# Qwiic_Shield_for_Teensy_Extended.net
KiCad netlist of a schematic drawn in EAGLE
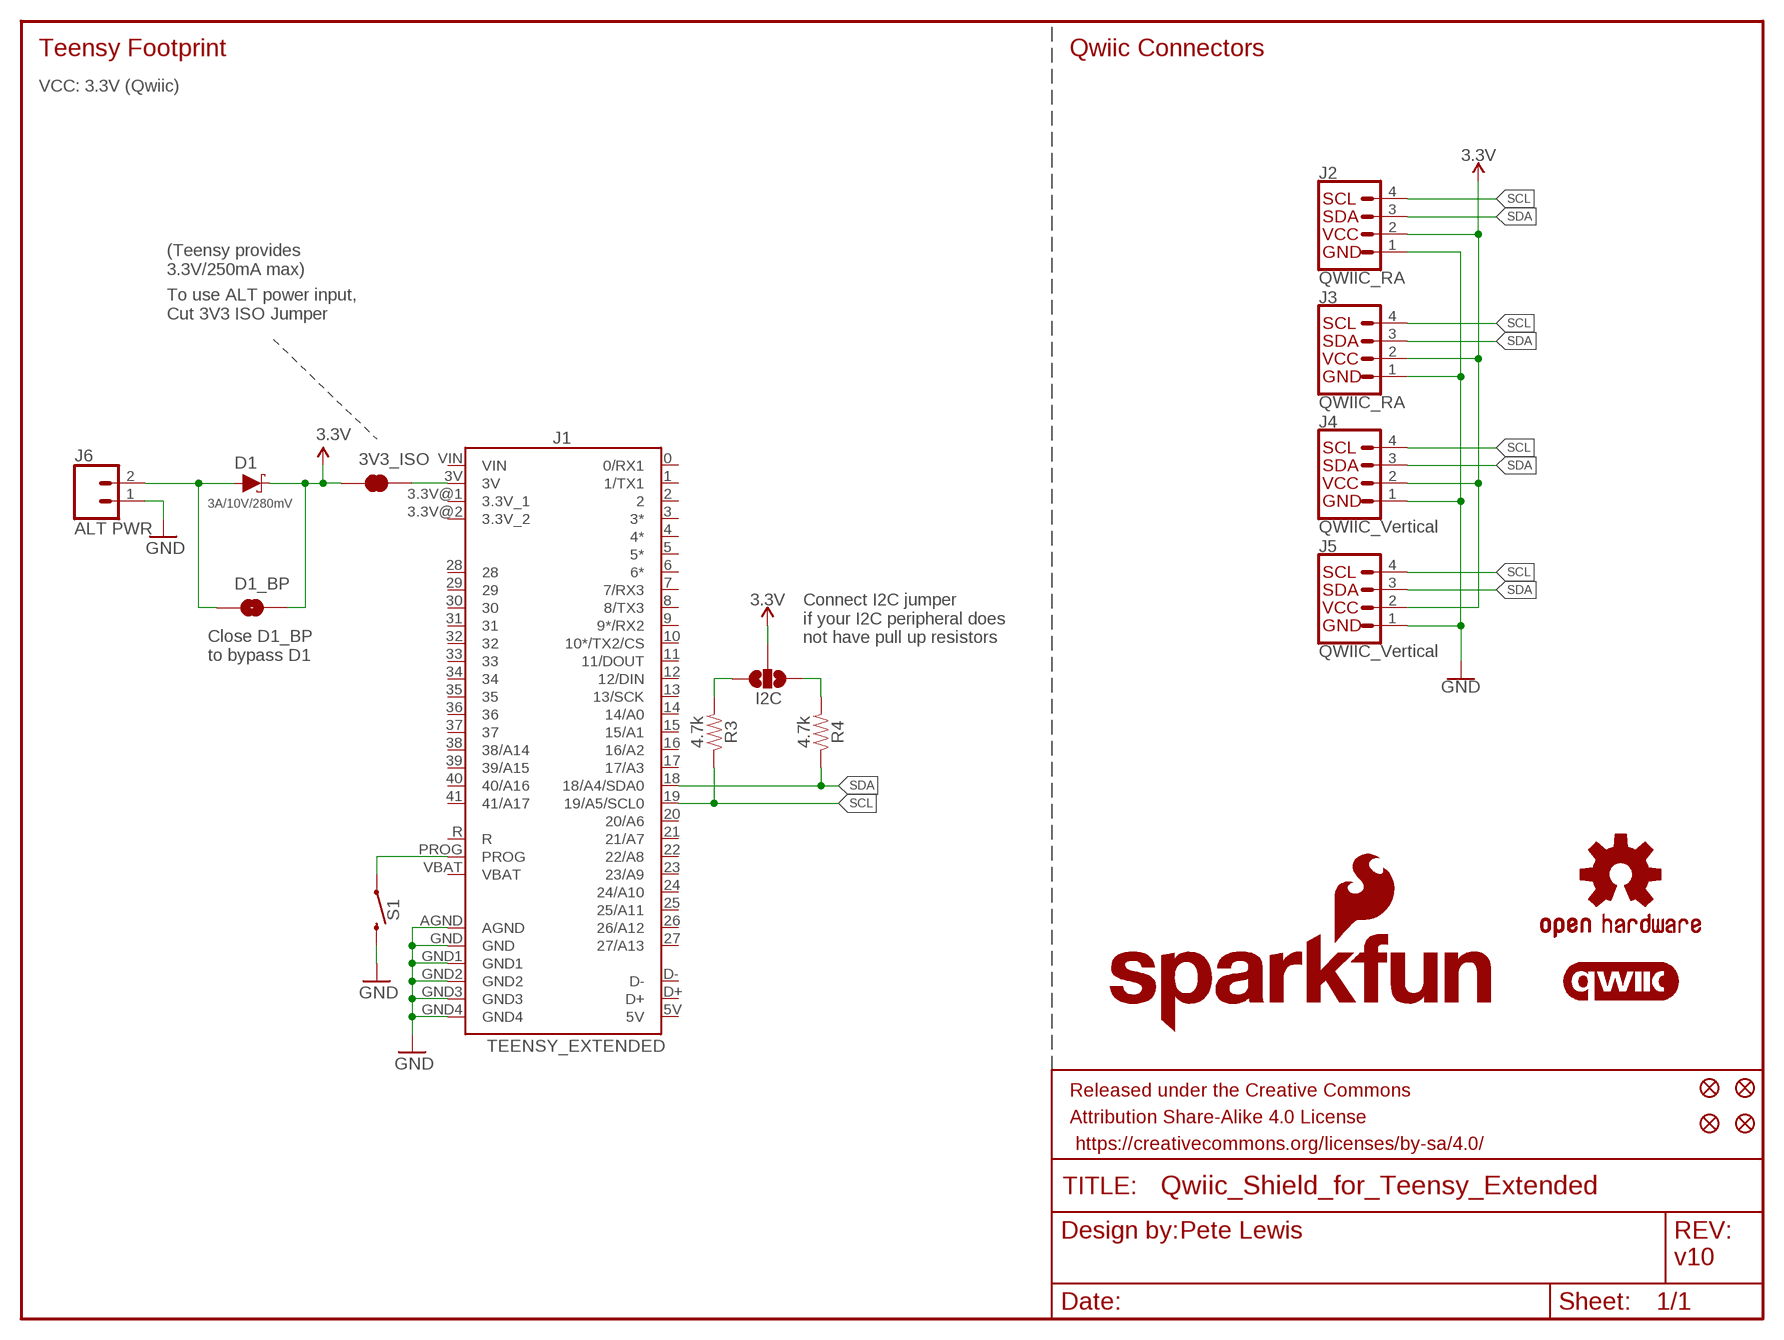
[diagram p0: schematic, sheet 1]

(export (version "E")
  (design (tool "Eeschema 10.0.6"))
  (components
    (comp (ref "3V3_ISO")
      (value "JUMPER-SMT_2_NC_TRACE_SILK")
      (footprint "eagle-import:SMT-JUMPER_2_NC_TRACE_SILK")
      (libsource (lib "eagle-import") (part "JUMPER-SMT_2_NC_TRACE_SILK"))
    )
    (comp (ref "D1")
      (value "3A/10V/280mV")
      (footprint "eagle-import:SOD-323")
      (libsource (lib "eagle-import") (part "DIODE-SCHOTTKY-BAT60A"))
    )
    (comp (ref "D1_BP")
      (value "JUMPER-SMT_2_NO_SILK")
      (footprint "eagle-import:SMT-JUMPER_2_NO_SILK")
      (libsource (lib "eagle-import") (part "JUMPER-SMT_2_NO_SILK"))
    )
    (comp (ref "FD1")
      (value "FIDUCIAL1X2")
      (footprint "eagle-import:FIDUCIAL-1X2")
      (libsource (lib "eagle-import") (part "FIDUCIAL1X2"))
    )
    (comp (ref "FD2")
      (value "FIDUCIAL1X2")
      (footprint "eagle-import:FIDUCIAL-1X2")
      (libsource (lib "eagle-import") (part "FIDUCIAL1X2"))
    )
    (comp (ref "FD3")
      (value "FIDUCIAL1X2")
      (footprint "eagle-import:FIDUCIAL-1X2")
      (libsource (lib "eagle-import") (part "FIDUCIAL1X2"))
    )
    (comp (ref "FD4")
      (value "FIDUCIAL1X2")
      (footprint "eagle-import:FIDUCIAL-1X2")
      (libsource (lib "eagle-import") (part "FIDUCIAL1X2"))
    )
    (comp (ref "FRAME1")
      (value "FRAME-LETTER")
      (footprint "eagle-import:CREATIVE_COMMONS")
      (libsource (lib "eagle-import") (part "FRAME-LETTER"))
    )
    (comp (ref "I2C")
      (value "JUMPER-SMT_3_NO_SILK")
      (footprint "eagle-import:SMT-JUMPER_3_NO_SILK")
      (libsource (lib "eagle-import") (part "JUMPER-SMT_3_NO_SILK"))
    )
    (comp (ref "J1")
      (value "TEENSY_EXTENDED")
      (footprint "eagle-import:TEENSY_EXTENDED_NO_SILK")
      (libsource (lib "eagle-import") (part "TEENSY_EXTENDEDNO_SILK"))
    )
    (comp (ref "J2")
      (value "QWIIC_RA")
      (footprint "eagle-import:JST04_1MM_RA")
      (libsource (lib "eagle-import") (part "QWIIC_CONNECTORJS-1MM"))
    )
    (comp (ref "J3")
      (value "QWIIC_RA")
      (footprint "eagle-import:JST04_1MM_RA")
      (libsource (lib "eagle-import") (part "QWIIC_CONNECTORJS-1MM"))
    )
    (comp (ref "J4")
      (value "QWIIC_Vertical")
      (footprint "eagle-import:JST04_1MM_VERT")
      (libsource (lib "eagle-import") (part "QWIIC_CONNECTOR"))
    )
    (comp (ref "J5")
      (value "QWIIC_Vertical")
      (footprint "eagle-import:JST04_1MM_VERT")
      (libsource (lib "eagle-import") (part "QWIIC_CONNECTOR"))
    )
    (comp (ref "J6")
      (value "ALT PWR")
      (footprint "eagle-import:1X02_NO_SILK")
      (libsource (lib "eagle-import") (part "CONN_021X02_NO_SILK"))
    )
    (comp (ref "LOGO1")
      (value "SFE_LOGO_NAME_FLAME.1_INCH")
      (footprint "eagle-import:SFE_LOGO_NAME_FLAME_.1")
      (libsource (lib "eagle-import") (part "SFE_LOGO_NAME_FLAME.1_INCH"))
    )
    (comp (ref "LOGO2")
      (value "SFE_LOGO_NAME_FLAME.1_INCH")
      (footprint "eagle-import:SFE_LOGO_NAME_FLAME_.1")
      (libsource (lib "eagle-import") (part "SFE_LOGO_NAME_FLAME.1_INCH"))
    )
    (comp (ref "LOGO3")
      (value "OSHW-LOGOS")
      (footprint "eagle-import:OSHW-LOGO-S")
      (libsource (lib "eagle-import") (part "OSHW-LOGOS"))
    )
    (comp (ref "LOGO4")
      (value "QWIIC_LOGO_5MM")
      (footprint "eagle-import:QWIIC_5MM")
      (libsource (lib "eagle-import") (part "QWIIC_LOGO_5MM"))
    )
    (comp (ref "LOGO5")
      (value "QWIIC_LOGO_5MM")
      (footprint "eagle-import:QWIIC_5MM")
      (libsource (lib "eagle-import") (part "QWIIC_LOGO_5MM"))
    )
    (comp (ref "R3")
      (value "4.7k")
      (footprint "eagle-import:0603")
      (libsource (lib "eagle-import") (part "4.7KOHM-0603-1/10W-1%"))
    )
    (comp (ref "R4")
      (value "4.7k")
      (footprint "eagle-import:0603")
      (libsource (lib "eagle-import") (part "4.7KOHM-0603-1/10W-1%"))
    )
    (comp (ref "S1")
      (value "SMD_5.2MM")
      (footprint "eagle-import:TACTILE_SWITCH_SMD_5.2MM")
      (libsource (lib "eagle-import") (part "MOMENTARY-SWITCH-SPST-SMD-5.2MM-TALL"))
    )
  )
  (nets
    (net (code "1") (name "/3.3V_1") (class "Default")
      (node (ref "J1") (pin "3.3V@1") (pinfunction "3.3V_1_3.3V@1") (pintype "power_in"))
    )
    (net (code "2") (name "/3.3V_2") (class "Default")
      (node (ref "J1") (pin "3.3V@2") (pinfunction "3.3V_2_3.3V@2") (pintype "power_in"))
    )
    (net (code "3") (name "/5V") (class "Default")
      (node (ref "J1") (pin "5V") (pinfunction "5V_5V") (pintype "power_in"))
    )
    (net (code "4") (name "/D+") (class "Default")
      (node (ref "J1") (pin "D+") (pinfunction "D+_D+") (pintype "power_in"))
    )
    (net (code "5") (name "/D-") (class "Default")
      (node (ref "J1") (pin "D-") (pinfunction "D-_D-") (pintype "power_in"))
    )
    (net (code "6") (name "/VBAT") (class "Default")
      (node (ref "J1") (pin "VBAT") (pinfunction "VBAT_VBAT") (pintype "power_in"))
    )
    (net (code "7") (name "/VIN") (class "Default")
      (node (ref "J1") (pin "VIN") (pinfunction "VIN_VIN") (pintype "power_in"))
    )
    (net (code "8") (name "3.3V") (class "Default")
      (node (ref "3V3_ISO") (pin "1") (pinfunction "1_1") (pintype "passive"))
      (node (ref "D1") (pin "C") (pinfunction "C_C") (pintype "passive"))
      (node (ref "D1_BP") (pin "2") (pinfunction "2_2") (pintype "passive"))
      (node (ref "I2C") (pin "2") (pinfunction "2_2") (pintype "passive"))
      (node (ref "J2") (pin "2") (pinfunction "2_2") (pintype "power_in"))
      (node (ref "J3") (pin "2") (pinfunction "2_2") (pintype "power_in"))
      (node (ref "J4") (pin "2") (pinfunction "2_2") (pintype "power_in"))
      (node (ref "J5") (pin "2") (pinfunction "2_2") (pintype "power_in"))
    )
    (net (code "9") (name "GND") (class "Default")
      (node (ref "J1") (pin "AGND") (pinfunction "AGND_AGND") (pintype "power_in"))
      (node (ref "J1") (pin "GND") (pinfunction "GND_GND") (pintype "power_in"))
      (node (ref "J1") (pin "GND1") (pinfunction "GND1_GND1") (pintype "power_in"))
      (node (ref "J1") (pin "GND2") (pinfunction "GND2_GND2") (pintype "power_in"))
      (node (ref "J1") (pin "GND3") (pinfunction "GND3_GND3") (pintype "power_in"))
      (node (ref "J1") (pin "GND4") (pinfunction "GND4_GND4") (pintype "bidirectional"))
      (node (ref "J2") (pin "1") (pinfunction "1_1") (pintype "power_in"))
      (node (ref "J3") (pin "1") (pinfunction "1_1") (pintype "power_in"))
      (node (ref "J4") (pin "1") (pinfunction "1_1") (pintype "power_in"))
      (node (ref "J5") (pin "1") (pinfunction "1_1") (pintype "power_in"))
      (node (ref "J6") (pin "1") (pinfunction "1_1") (pintype "passive"))
      (node (ref "S1") (pin "3") (pinfunction "2_3") (pintype "passive"))
    )
    (net (code "10") (name "Net-(3V3_ISO-Pad2)") (class "Default")
      (node (ref "3V3_ISO") (pin "2") (pinfunction "2_2") (pintype "passive"))
      (node (ref "J1") (pin "3V") (pinfunction "3V_3V") (pintype "power_in"))
    )
    (net (code "11") (name "Net-(D1-PadA)") (class "Default")
      (node (ref "D1") (pin "A") (pinfunction "A_A") (pintype "passive"))
      (node (ref "D1_BP") (pin "1") (pinfunction "1_1") (pintype "passive"))
      (node (ref "J6") (pin "2") (pinfunction "2_2") (pintype "passive"))
    )
    (net (code "12") (name "Net-(I2C-Pad1)") (class "Default")
      (node (ref "I2C") (pin "1") (pinfunction "1_1") (pintype "passive"))
      (node (ref "R3") (pin "2") (pinfunction "2_2") (pintype "passive"))
    )
    (net (code "13") (name "Net-(I2C-Pad3)") (class "Default")
      (node (ref "I2C") (pin "3") (pinfunction "3_3") (pintype "passive"))
      (node (ref "R4") (pin "2") (pinfunction "2_2") (pintype "passive"))
    )
    (net (code "14") (name "Net-(J1-PadPROG)") (class "Default")
      (node (ref "J1") (pin "PROG") (pinfunction "PROG_PROG") (pintype "bidirectional"))
      (node (ref "S1") (pin "1") (pinfunction "1_1") (pintype "passive"))
    )
    (net (code "15") (name "SCL") (class "Default")
      (node (ref "J1") (pin "19") (pinfunction "19/A5/SCL0_19") (pintype "bidirectional"))
      (node (ref "J2") (pin "4") (pinfunction "4_4") (pintype "passive"))
      (node (ref "J3") (pin "4") (pinfunction "4_4") (pintype "passive"))
      (node (ref "J4") (pin "4") (pinfunction "4_4") (pintype "passive"))
      (node (ref "J5") (pin "4") (pinfunction "4_4") (pintype "passive"))
      (node (ref "R3") (pin "1") (pinfunction "1_1") (pintype "passive"))
    )
    (net (code "16") (name "SDA") (class "Default")
      (node (ref "J1") (pin "18") (pinfunction "18/A4/SDA0_18") (pintype "bidirectional"))
      (node (ref "J2") (pin "3") (pinfunction "3_3") (pintype "passive"))
      (node (ref "J3") (pin "3") (pinfunction "3_3") (pintype "passive"))
      (node (ref "J4") (pin "3") (pinfunction "3_3") (pintype "passive"))
      (node (ref "J5") (pin "3") (pinfunction "3_3") (pintype "passive"))
      (node (ref "R4") (pin "1") (pinfunction "1_1") (pintype "passive"))
    )
    (net (code "17") (name "unconnected-(J1-0{slash}RX1-Pad0)") (class "Default")
      (node (ref "J1") (pin "0") (pinfunction "0/RX1_0") (pintype "bidirectional"))
    )
    (net (code "18") (name "unconnected-(J1-1{slash}TX1-Pad1)") (class "Default")
      (node (ref "J1") (pin "1") (pinfunction "1/TX1_1") (pintype "bidirectional"))
    )
    (net (code "19") (name "unconnected-(J1-3*-Pad3)") (class "Default")
      (node (ref "J1") (pin "3") (pinfunction "3*_3") (pintype "bidirectional"))
    )
    (net (code "20") (name "unconnected-(J1-4*-Pad4)") (class "Default")
      (node (ref "J1") (pin "4") (pinfunction "4*_4") (pintype "bidirectional"))
    )
    (net (code "21") (name "unconnected-(J1-5*-Pad5)") (class "Default")
      (node (ref "J1") (pin "5") (pinfunction "5*_5") (pintype "bidirectional"))
    )
    (net (code "22") (name "unconnected-(J1-6*-Pad6)") (class "Default")
      (node (ref "J1") (pin "6") (pinfunction "6*_6") (pintype "bidirectional"))
    )
    (net (code "23") (name "unconnected-(J1-7{slash}RX3-Pad7)") (class "Default")
      (node (ref "J1") (pin "7") (pinfunction "7/RX3_7") (pintype "bidirectional"))
    )
    (net (code "24") (name "unconnected-(J1-8{slash}TX3-Pad8)") (class "Default")
      (node (ref "J1") (pin "8") (pinfunction "8/TX3_8") (pintype "bidirectional"))
    )
    (net (code "25") (name "unconnected-(J1-9*{slash}RX2-Pad9)") (class "Default")
      (node (ref "J1") (pin "9") (pinfunction "9*/RX2_9") (pintype "bidirectional"))
    )
    (net (code "26") (name "unconnected-(J1-10*{slash}TX2{slash}CS-Pad10)") (class "Default")
      (node (ref "J1") (pin "10") (pinfunction "10*/TX2/CS_10") (pintype "bidirectional"))
    )
    (net (code "27") (name "unconnected-(J1-11{slash}DOUT-Pad11)") (class "Default")
      (node (ref "J1") (pin "11") (pinfunction "11/DOUT_11") (pintype "bidirectional"))
    )
    (net (code "28") (name "unconnected-(J1-12{slash}DIN-Pad12)") (class "Default")
      (node (ref "J1") (pin "12") (pinfunction "12/DIN_12") (pintype "bidirectional"))
    )
    (net (code "29") (name "unconnected-(J1-13{slash}SCK-Pad13)") (class "Default")
      (node (ref "J1") (pin "13") (pinfunction "13/SCK_13") (pintype "bidirectional"))
    )
    (net (code "30") (name "unconnected-(J1-14{slash}A0-Pad14)") (class "Default")
      (node (ref "J1") (pin "14") (pinfunction "14/A0_14") (pintype "bidirectional"))
    )
    (net (code "31") (name "unconnected-(J1-15{slash}A1-Pad15)") (class "Default")
      (node (ref "J1") (pin "15") (pinfunction "15/A1_15") (pintype "bidirectional"))
    )
    (net (code "32") (name "unconnected-(J1-16{slash}A2-Pad16)") (class "Default")
      (node (ref "J1") (pin "16") (pinfunction "16/A2_16") (pintype "bidirectional"))
    )
    (net (code "33") (name "unconnected-(J1-17{slash}A3-Pad17)") (class "Default")
      (node (ref "J1") (pin "17") (pinfunction "17/A3_17") (pintype "bidirectional"))
    )
    (net (code "34") (name "unconnected-(J1-20{slash}A6-Pad20)") (class "Default")
      (node (ref "J1") (pin "20") (pinfunction "20/A6_20") (pintype "bidirectional"))
    )
    (net (code "35") (name "unconnected-(J1-21{slash}A7-Pad21)") (class "Default")
      (node (ref "J1") (pin "21") (pinfunction "21/A7_21") (pintype "bidirectional"))
    )
    (net (code "36") (name "unconnected-(J1-22{slash}A8-Pad22)") (class "Default")
      (node (ref "J1") (pin "22") (pinfunction "22/A8_22") (pintype "bidirectional"))
    )
    (net (code "37") (name "unconnected-(J1-23{slash}A9-Pad23)") (class "Default")
      (node (ref "J1") (pin "23") (pinfunction "23/A9_23") (pintype "bidirectional"))
    )
    (net (code "38") (name "unconnected-(J1-24{slash}A10-Pad24)") (class "Default")
      (node (ref "J1") (pin "24") (pinfunction "24/A10_24") (pintype "bidirectional"))
    )
    (net (code "39") (name "unconnected-(J1-25{slash}A11-Pad25)") (class "Default")
      (node (ref "J1") (pin "25") (pinfunction "25/A11_25") (pintype "bidirectional"))
    )
    (net (code "40") (name "unconnected-(J1-26{slash}A12-Pad26)") (class "Default")
      (node (ref "J1") (pin "26") (pinfunction "26/A12_26") (pintype "bidirectional"))
    )
    (net (code "41") (name "unconnected-(J1-27{slash}A13-Pad27)") (class "Default")
      (node (ref "J1") (pin "27") (pinfunction "27/A13_27") (pintype "bidirectional"))
    )
    (net (code "42") (name "unconnected-(J1-38{slash}A14-Pad38)") (class "Default")
      (node (ref "J1") (pin "38") (pinfunction "38/A14_38") (pintype "bidirectional"))
    )
    (net (code "43") (name "unconnected-(J1-39{slash}A15-Pad39)") (class "Default")
      (node (ref "J1") (pin "39") (pinfunction "39/A15_39") (pintype "bidirectional"))
    )
    (net (code "44") (name "unconnected-(J1-40{slash}A16-Pad40)") (class "Default")
      (node (ref "J1") (pin "40") (pinfunction "40/A16_40") (pintype "bidirectional"))
    )
    (net (code "45") (name "unconnected-(J1-41{slash}A17-Pad41)") (class "Default")
      (node (ref "J1") (pin "41") (pinfunction "41/A17_41") (pintype "bidirectional"))
    )
    (net (code "46") (name "unconnected-(J1-Pad2)") (class "Default")
      (node (ref "J1") (pin "2") (pinfunction "2_2") (pintype "bidirectional"))
    )
    (net (code "47") (name "unconnected-(J1-Pad28)") (class "Default")
      (node (ref "J1") (pin "28") (pinfunction "28_28") (pintype "bidirectional"))
    )
    (net (code "48") (name "unconnected-(J1-Pad29)") (class "Default")
      (node (ref "J1") (pin "29") (pinfunction "29_29") (pintype "bidirectional"))
    )
    (net (code "49") (name "unconnected-(J1-Pad30)") (class "Default")
      (node (ref "J1") (pin "30") (pinfunction "30_30") (pintype "bidirectional"))
    )
    (net (code "50") (name "unconnected-(J1-Pad31)") (class "Default")
      (node (ref "J1") (pin "31") (pinfunction "31_31") (pintype "bidirectional"))
    )
    (net (code "51") (name "unconnected-(J1-Pad32)") (class "Default")
      (node (ref "J1") (pin "32") (pinfunction "32_32") (pintype "bidirectional"))
    )
    (net (code "52") (name "unconnected-(J1-Pad33)") (class "Default")
      (node (ref "J1") (pin "33") (pinfunction "33_33") (pintype "bidirectional"))
    )
    (net (code "53") (name "unconnected-(J1-Pad34)") (class "Default")
      (node (ref "J1") (pin "34") (pinfunction "34_34") (pintype "bidirectional"))
    )
    (net (code "54") (name "unconnected-(J1-Pad35)") (class "Default")
      (node (ref "J1") (pin "35") (pinfunction "35_35") (pintype "bidirectional"))
    )
    (net (code "55") (name "unconnected-(J1-Pad36)") (class "Default")
      (node (ref "J1") (pin "36") (pinfunction "36_36") (pintype "bidirectional"))
    )
    (net (code "56") (name "unconnected-(J1-Pad37)") (class "Default")
      (node (ref "J1") (pin "37") (pinfunction "37_37") (pintype "bidirectional"))
    )
    (net (code "57") (name "unconnected-(J1-PadR)") (class "Default")
      (node (ref "J1") (pin "R") (pinfunction "R_R") (pintype "bidirectional"))
    )
  )
)
